# fmc.net
KiCad netlist of a schematic drawn in EAGLE
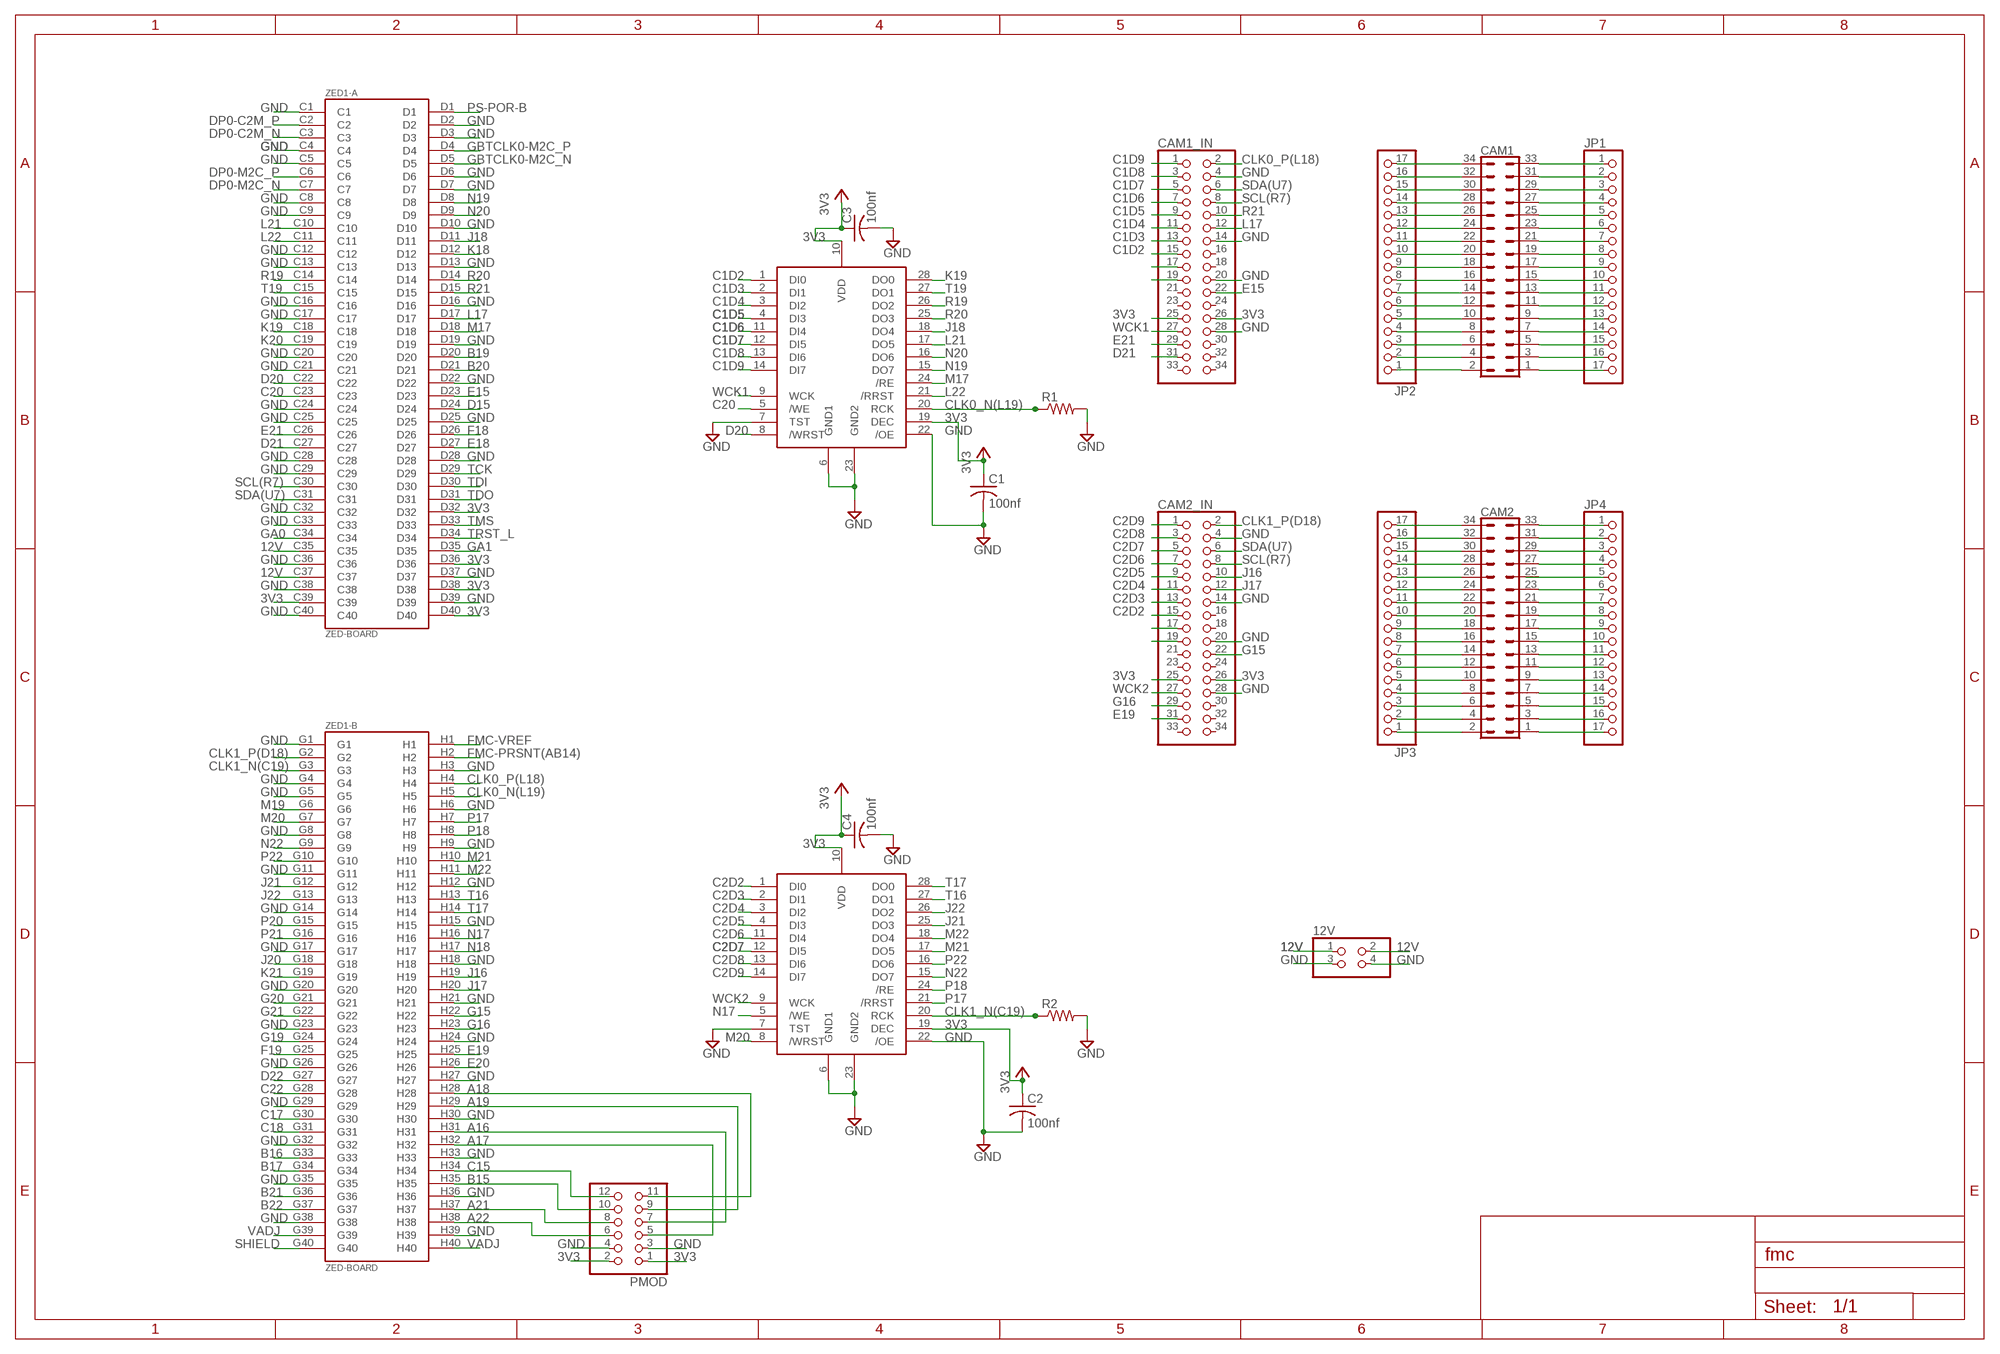
[diagram p0: schematic, sheet 1]

(export (version "E")
  (design (tool "Eeschema 10.0.6"))
  (components
    (comp (ref "12V")
      (value "PINHD-2X2")
      (footprint "eagle-import:2X02")
      (libsource (lib "eagle-import") (part "PINHD-2X2"))
    )
    (comp (ref "AL422B")
      (value "CAM1_FIFO")
      (footprint "eagle-import:SOP28")
      (libsource (lib "eagle-import") (part "AL422B"))
    )
    (comp (ref "C1")
      (value "100nf")
      (footprint "eagle-import:C025-024X044")
      (libsource (lib "eagle-import") (part "C-US025-024X044"))
    )
    (comp (ref "C2")
      (value "100nf")
      (footprint "eagle-import:C025-024X044")
      (libsource (lib "eagle-import") (part "C-US025-024X044"))
    )
    (comp (ref "C3")
      (value "100nf")
      (footprint "eagle-import:C025-024X044")
      (libsource (lib "eagle-import") (part "C-US025-024X044"))
    )
    (comp (ref "C4")
      (value "100nf")
      (footprint "eagle-import:C025-024X044")
      (libsource (lib "eagle-import") (part "C-US025-024X044"))
    )
    (comp (ref "CAM1")
      (value "PHB_1MM27_2X17_SNT")
      (footprint "eagle-import:PHB_1MM27_2X17_SNT")
      (libsource (lib "eagle-import") (part "PHB_1MM27_2X17_SNT"))
    )
    (comp (ref "CAM1_IN")
      (value "PINHD-2X17")
      (footprint "eagle-import:2X17")
      (libsource (lib "eagle-import") (part "PINHD-2X17"))
    )
    (comp (ref "CAM2")
      (value "PHB_1MM27_2X17_SNT")
      (footprint "eagle-import:PHB_1MM27_2X17_SNT")
      (libsource (lib "eagle-import") (part "PHB_1MM27_2X17_SNT"))
    )
    (comp (ref "CAM2_IN")
      (value "PINHD-2X17")
      (footprint "eagle-import:2X17")
      (libsource (lib "eagle-import") (part "PINHD-2X17"))
    )
    (comp (ref "JP1")
      (value "PINHD-1X17")
      (footprint "eagle-import:1X17")
      (libsource (lib "eagle-import") (part "PINHD-1X17"))
    )
    (comp (ref "JP2")
      (value "PINHD-1X17")
      (footprint "eagle-import:1X17")
      (libsource (lib "eagle-import") (part "PINHD-1X17"))
    )
    (comp (ref "JP3")
      (value "PINHD-1X17")
      (footprint "eagle-import:1X17")
      (libsource (lib "eagle-import") (part "PINHD-1X17"))
    )
    (comp (ref "JP4")
      (value "PINHD-1X17")
      (footprint "eagle-import:1X17")
      (libsource (lib "eagle-import") (part "PINHD-1X17"))
    )
    (comp (ref "PMOD")
      (value "PINHD-2X6")
      (footprint "eagle-import:2X06")
      (libsource (lib "eagle-import") (part "PINHD-2X6"))
    )
    (comp (ref "R1")
      (value "R-US_M0805")
      (footprint "eagle-import:M0805")
      (libsource (lib "eagle-import") (part "R-US_M0805"))
    )
    (comp (ref "R2")
      (value "R-US_M0805")
      (footprint "eagle-import:M0805")
      (libsource (lib "eagle-import") (part "R-US_M0805"))
    )
    (comp (ref "U$2")
      (value "CAM2_FIFO")
      (footprint "eagle-import:SOP28")
      (libsource (lib "eagle-import") (part "AL422B"))
    )
    (comp (ref "ZED1")
      (value "ZED-BOARD")
      (footprint "eagle-import:ASP-134604-01")
      (libsource (lib "eagle-import") (part "ZED-BOARD"))
    )
  )
  (nets
    (net (code "1") (name "/12V") (class "Default")
      (node (ref "12V") (pin "1") (pinfunction "1_1") (pintype "passive"))
      (node (ref "12V") (pin "2") (pinfunction "2_2") (pintype "passive"))
      (node (ref "ZED1") (pin "C35") (pinfunction "C35_C35") (pintype "bidirectional"))
      (node (ref "ZED1") (pin "C37") (pinfunction "C37_C37") (pintype "bidirectional"))
    )
    (net (code "2") (name "/A16") (class "Default")
      (node (ref "PMOD") (pin "7") (pinfunction "7_7") (pintype "passive"))
      (node (ref "ZED1") (pin "H31") (pinfunction "H31_H31") (pintype "bidirectional"))
    )
    (net (code "3") (name "/A17") (class "Default")
      (node (ref "PMOD") (pin "5") (pinfunction "5_5") (pintype "passive"))
      (node (ref "ZED1") (pin "H32") (pinfunction "H32_H32") (pintype "bidirectional"))
    )
    (net (code "4") (name "/A18") (class "Default")
      (node (ref "PMOD") (pin "11") (pinfunction "11_11") (pintype "passive"))
      (node (ref "ZED1") (pin "H28") (pinfunction "H28_H28") (pintype "bidirectional"))
    )
    (net (code "5") (name "/A19") (class "Default")
      (node (ref "PMOD") (pin "9") (pinfunction "9_9") (pintype "passive"))
      (node (ref "ZED1") (pin "H29") (pinfunction "H29_H29") (pintype "bidirectional"))
    )
    (net (code "6") (name "/A21") (class "Default")
      (node (ref "PMOD") (pin "8") (pinfunction "8_8") (pintype "passive"))
      (node (ref "ZED1") (pin "H37") (pinfunction "H37_H37") (pintype "bidirectional"))
    )
    (net (code "7") (name "/A22") (class "Default")
      (node (ref "PMOD") (pin "6") (pinfunction "6_6") (pintype "passive"))
      (node (ref "ZED1") (pin "H38") (pinfunction "H38_H38") (pintype "bidirectional"))
    )
    (net (code "8") (name "/B15") (class "Default")
      (node (ref "PMOD") (pin "10") (pinfunction "10_10") (pintype "passive"))
      (node (ref "ZED1") (pin "H35") (pinfunction "H35_H35") (pintype "bidirectional"))
    )
    (net (code "9") (name "/B16") (class "Default")
      (node (ref "ZED1") (pin "G33") (pinfunction "G33_G33") (pintype "bidirectional"))
    )
    (net (code "10") (name "/B17") (class "Default")
      (node (ref "ZED1") (pin "G34") (pinfunction "G34_G34") (pintype "bidirectional"))
    )
    (net (code "11") (name "/B19") (class "Default")
      (node (ref "ZED1") (pin "D20") (pinfunction "D20_D20") (pintype "bidirectional"))
    )
    (net (code "12") (name "/B20") (class "Default")
      (node (ref "ZED1") (pin "D21") (pinfunction "D21_D21") (pintype "bidirectional"))
    )
    (net (code "13") (name "/B21") (class "Default")
      (node (ref "ZED1") (pin "G36") (pinfunction "G36_G36") (pintype "bidirectional"))
    )
    (net (code "14") (name "/B22") (class "Default")
      (node (ref "ZED1") (pin "G37") (pinfunction "G37_G37") (pintype "bidirectional"))
    )
    (net (code "15") (name "/C1D2") (class "Default")
      (node (ref "AL422B") (pin "1") (pinfunction "DI0_1") (pintype "bidirectional"))
      (node (ref "CAM1_IN") (pin "15") (pinfunction "15_15") (pintype "passive"))
    )
    (net (code "16") (name "/C1D3") (class "Default")
      (node (ref "AL422B") (pin "2") (pinfunction "DI1_2") (pintype "bidirectional"))
      (node (ref "CAM1_IN") (pin "13") (pinfunction "13_13") (pintype "passive"))
    )
    (net (code "17") (name "/C1D4") (class "Default")
      (node (ref "AL422B") (pin "3") (pinfunction "DI2_3") (pintype "bidirectional"))
      (node (ref "CAM1_IN") (pin "11") (pinfunction "11_11") (pintype "passive"))
    )
    (net (code "18") (name "/C1D5") (class "Default")
      (node (ref "AL422B") (pin "4") (pinfunction "DI3_4") (pintype "bidirectional"))
      (node (ref "CAM1_IN") (pin "9") (pinfunction "9_9") (pintype "passive"))
    )
    (net (code "19") (name "/C1D6") (class "Default")
      (node (ref "AL422B") (pin "11") (pinfunction "DI4_11") (pintype "bidirectional"))
      (node (ref "CAM1_IN") (pin "7") (pinfunction "7_7") (pintype "passive"))
    )
    (net (code "20") (name "/C1D7") (class "Default")
      (node (ref "AL422B") (pin "12") (pinfunction "DI5_12") (pintype "bidirectional"))
      (node (ref "CAM1_IN") (pin "5") (pinfunction "5_5") (pintype "passive"))
    )
    (net (code "21") (name "/C1D8") (class "Default")
      (node (ref "AL422B") (pin "13") (pinfunction "DI6_13") (pintype "bidirectional"))
      (node (ref "CAM1_IN") (pin "3") (pinfunction "3_3") (pintype "passive"))
    )
    (net (code "22") (name "/C1D9") (class "Default")
      (node (ref "AL422B") (pin "14") (pinfunction "DI7_14") (pintype "bidirectional"))
      (node (ref "CAM1_IN") (pin "1") (pinfunction "1_1") (pintype "passive"))
    )
    (net (code "23") (name "/C2D2") (class "Default")
      (node (ref "CAM2_IN") (pin "15") (pinfunction "15_15") (pintype "passive"))
      (node (ref "U$2") (pin "1") (pinfunction "DI0_1") (pintype "bidirectional"))
    )
    (net (code "24") (name "/C2D3") (class "Default")
      (node (ref "CAM2_IN") (pin "13") (pinfunction "13_13") (pintype "passive"))
      (node (ref "U$2") (pin "2") (pinfunction "DI1_2") (pintype "bidirectional"))
    )
    (net (code "25") (name "/C2D4") (class "Default")
      (node (ref "CAM2_IN") (pin "11") (pinfunction "11_11") (pintype "passive"))
      (node (ref "U$2") (pin "3") (pinfunction "DI2_3") (pintype "bidirectional"))
    )
    (net (code "26") (name "/C2D5") (class "Default")
      (node (ref "CAM2_IN") (pin "9") (pinfunction "9_9") (pintype "passive"))
      (node (ref "U$2") (pin "4") (pinfunction "DI3_4") (pintype "bidirectional"))
    )
    (net (code "27") (name "/C2D6") (class "Default")
      (node (ref "CAM2_IN") (pin "7") (pinfunction "7_7") (pintype "passive"))
      (node (ref "U$2") (pin "11") (pinfunction "DI4_11") (pintype "bidirectional"))
    )
    (net (code "28") (name "/C2D7") (class "Default")
      (node (ref "CAM2_IN") (pin "5") (pinfunction "5_5") (pintype "passive"))
      (node (ref "U$2") (pin "12") (pinfunction "DI5_12") (pintype "bidirectional"))
    )
    (net (code "29") (name "/C2D8") (class "Default")
      (node (ref "CAM2_IN") (pin "3") (pinfunction "3_3") (pintype "passive"))
      (node (ref "U$2") (pin "13") (pinfunction "DI6_13") (pintype "bidirectional"))
    )
    (net (code "30") (name "/C2D9") (class "Default")
      (node (ref "CAM2_IN") (pin "1") (pinfunction "1_1") (pintype "passive"))
      (node (ref "U$2") (pin "14") (pinfunction "DI7_14") (pintype "bidirectional"))
    )
    (net (code "31") (name "/C15") (class "Default")
      (node (ref "PMOD") (pin "12") (pinfunction "12_12") (pintype "passive"))
      (node (ref "ZED1") (pin "H34") (pinfunction "H34_H34") (pintype "bidirectional"))
    )
    (net (code "32") (name "/C17") (class "Default")
      (node (ref "ZED1") (pin "G30") (pinfunction "G30_G30") (pintype "bidirectional"))
    )
    (net (code "33") (name "/C18") (class "Default")
      (node (ref "ZED1") (pin "G31") (pinfunction "G31_G31") (pintype "bidirectional"))
    )
    (net (code "34") (name "/C20") (class "Default")
      (node (ref "AL422B") (pin "5") (pinfunction "/WE_5") (pintype "bidirectional"))
      (node (ref "ZED1") (pin "C23") (pinfunction "C23_C23") (pintype "bidirectional"))
    )
    (net (code "35") (name "/C22") (class "Default")
      (node (ref "ZED1") (pin "G28") (pinfunction "G28_G28") (pintype "bidirectional"))
    )
    (net (code "36") (name "/CLK0_N(L19)") (class "Default")
      (node (ref "AL422B") (pin "20") (pinfunction "RCK_20") (pintype "bidirectional"))
      (node (ref "R1") (pin "1") (pinfunction "1_1") (pintype "passive"))
      (node (ref "ZED1") (pin "H5") (pinfunction "H5_H5") (pintype "bidirectional"))
    )
    (net (code "37") (name "/CLK0_P(L18)") (class "Default")
      (node (ref "CAM1_IN") (pin "2") (pinfunction "2_2") (pintype "passive"))
      (node (ref "ZED1") (pin "H4") (pinfunction "H4_H4") (pintype "bidirectional"))
    )
    (net (code "38") (name "/CLK1_N(C19)") (class "Default")
      (node (ref "R2") (pin "1") (pinfunction "1_1") (pintype "passive"))
      (node (ref "U$2") (pin "20") (pinfunction "RCK_20") (pintype "bidirectional"))
      (node (ref "ZED1") (pin "G3") (pinfunction "G3_G3") (pintype "bidirectional"))
    )
    (net (code "39") (name "/CLK1_P(D18)") (class "Default")
      (node (ref "CAM2_IN") (pin "2") (pinfunction "2_2") (pintype "passive"))
      (node (ref "ZED1") (pin "G2") (pinfunction "G2_G2") (pintype "bidirectional"))
    )
    (net (code "40") (name "/D15") (class "Default")
      (node (ref "ZED1") (pin "D24") (pinfunction "D24_D24") (pintype "bidirectional"))
    )
    (net (code "41") (name "/D20") (class "Default")
      (node (ref "AL422B") (pin "8") (pinfunction "/WRST_8") (pintype "bidirectional"))
      (node (ref "ZED1") (pin "C22") (pinfunction "C22_C22") (pintype "bidirectional"))
    )
    (net (code "42") (name "/D21") (class "Default")
      (node (ref "CAM1_IN") (pin "31") (pinfunction "31_31") (pintype "passive"))
      (node (ref "ZED1") (pin "C27") (pinfunction "C27_C27") (pintype "bidirectional"))
    )
    (net (code "43") (name "/D22") (class "Default")
      (node (ref "ZED1") (pin "G27") (pinfunction "G27_G27") (pintype "bidirectional"))
    )
    (net (code "44") (name "/DP0-C2M_N") (class "Default")
      (node (ref "ZED1") (pin "C3") (pinfunction "C3_C3") (pintype "bidirectional"))
    )
    (net (code "45") (name "/DP0-C2M_P") (class "Default")
      (node (ref "ZED1") (pin "C2") (pinfunction "C2_C2") (pintype "bidirectional"))
    )
    (net (code "46") (name "/DP0-M2C_N") (class "Default")
      (node (ref "ZED1") (pin "C7") (pinfunction "C7_C7") (pintype "bidirectional"))
    )
    (net (code "47") (name "/DP0-M2C_P") (class "Default")
      (node (ref "ZED1") (pin "C6") (pinfunction "C6_C6") (pintype "bidirectional"))
    )
    (net (code "48") (name "/E15") (class "Default")
      (node (ref "CAM1_IN") (pin "22") (pinfunction "22_22") (pintype "passive"))
      (node (ref "ZED1") (pin "D23") (pinfunction "D23_D23") (pintype "bidirectional"))
    )
    (net (code "49") (name "/E18") (class "Default")
      (node (ref "ZED1") (pin "D27") (pinfunction "D27_D27") (pintype "bidirectional"))
    )
    (net (code "50") (name "/E19") (class "Default")
      (node (ref "CAM2_IN") (pin "31") (pinfunction "31_31") (pintype "passive"))
      (node (ref "ZED1") (pin "H25") (pinfunction "H25_H25") (pintype "bidirectional"))
    )
    (net (code "51") (name "/E20") (class "Default")
      (node (ref "ZED1") (pin "H26") (pinfunction "H26_H26") (pintype "bidirectional"))
    )
    (net (code "52") (name "/E21") (class "Default")
      (node (ref "CAM1_IN") (pin "29") (pinfunction "29_29") (pintype "passive"))
      (node (ref "ZED1") (pin "C26") (pinfunction "C26_C26") (pintype "bidirectional"))
    )
    (net (code "53") (name "/F18") (class "Default")
      (node (ref "ZED1") (pin "D26") (pinfunction "D26_D26") (pintype "bidirectional"))
    )
    (net (code "54") (name "/F19") (class "Default")
      (node (ref "ZED1") (pin "G25") (pinfunction "G25_G25") (pintype "bidirectional"))
    )
    (net (code "55") (name "/FMC-PRSNT(AB14)") (class "Default")
      (node (ref "ZED1") (pin "H2") (pinfunction "H2_H2") (pintype "bidirectional"))
    )
    (net (code "56") (name "/FMC-VREF") (class "Default")
      (node (ref "ZED1") (pin "H1") (pinfunction "H1_H1") (pintype "bidirectional"))
    )
    (net (code "57") (name "/G15") (class "Default")
      (node (ref "CAM2_IN") (pin "22") (pinfunction "22_22") (pintype "passive"))
      (node (ref "ZED1") (pin "H22") (pinfunction "H22_H22") (pintype "bidirectional"))
    )
    (net (code "58") (name "/G16") (class "Default")
      (node (ref "CAM2_IN") (pin "29") (pinfunction "29_29") (pintype "passive"))
      (node (ref "ZED1") (pin "H23") (pinfunction "H23_H23") (pintype "bidirectional"))
    )
    (net (code "59") (name "/G19") (class "Default")
      (node (ref "ZED1") (pin "G24") (pinfunction "G24_G24") (pintype "bidirectional"))
    )
    (net (code "60") (name "/G20") (class "Default")
      (node (ref "ZED1") (pin "G21") (pinfunction "G21_G21") (pintype "bidirectional"))
    )
    (net (code "61") (name "/G21") (class "Default")
      (node (ref "ZED1") (pin "G22") (pinfunction "G22_G22") (pintype "bidirectional"))
    )
    (net (code "62") (name "/GA0") (class "Default")
      (node (ref "ZED1") (pin "C34") (pinfunction "C34_C34") (pintype "bidirectional"))
    )
    (net (code "63") (name "/GA1") (class "Default")
      (node (ref "ZED1") (pin "D35") (pinfunction "D35_D35") (pintype "bidirectional"))
    )
    (net (code "64") (name "/GBTCLK0-M2C_N") (class "Default")
      (node (ref "ZED1") (pin "D5") (pinfunction "D5_D5") (pintype "bidirectional"))
    )
    (net (code "65") (name "/GBTCLK0-M2C_P") (class "Default")
      (node (ref "ZED1") (pin "D4") (pinfunction "D4_D4") (pintype "bidirectional"))
    )
    (net (code "66") (name "/J16") (class "Default")
      (node (ref "CAM2_IN") (pin "10") (pinfunction "10_10") (pintype "passive"))
      (node (ref "ZED1") (pin "H19") (pinfunction "H19_H19") (pintype "bidirectional"))
    )
    (net (code "67") (name "/J17") (class "Default")
      (node (ref "CAM2_IN") (pin "12") (pinfunction "12_12") (pintype "passive"))
      (node (ref "ZED1") (pin "H20") (pinfunction "H20_H20") (pintype "bidirectional"))
    )
    (net (code "68") (name "/J18") (class "Default")
      (node (ref "AL422B") (pin "18") (pinfunction "DO4_18") (pintype "bidirectional"))
      (node (ref "ZED1") (pin "D11") (pinfunction "D11_D11") (pintype "bidirectional"))
    )
    (net (code "69") (name "/J20") (class "Default")
      (node (ref "ZED1") (pin "G18") (pinfunction "G18_G18") (pintype "bidirectional"))
    )
    (net (code "70") (name "/J21") (class "Default")
      (node (ref "U$2") (pin "25") (pinfunction "DO3_25") (pintype "bidirectional"))
      (node (ref "ZED1") (pin "G12") (pinfunction "G12_G12") (pintype "bidirectional"))
    )
    (net (code "71") (name "/J22") (class "Default")
      (node (ref "U$2") (pin "26") (pinfunction "DO2_26") (pintype "bidirectional"))
      (node (ref "ZED1") (pin "G13") (pinfunction "G13_G13") (pintype "bidirectional"))
    )
    (net (code "72") (name "/K18") (class "Default")
      (node (ref "ZED1") (pin "D12") (pinfunction "D12_D12") (pintype "bidirectional"))
    )
    (net (code "73") (name "/K19") (class "Default")
      (node (ref "AL422B") (pin "28") (pinfunction "DO0_28") (pintype "bidirectional"))
      (node (ref "ZED1") (pin "C18") (pinfunction "C18_C18") (pintype "bidirectional"))
    )
    (net (code "74") (name "/K20") (class "Default")
      (node (ref "ZED1") (pin "C19") (pinfunction "C19_C19") (pintype "bidirectional"))
    )
    (net (code "75") (name "/K21") (class "Default")
      (node (ref "ZED1") (pin "G19") (pinfunction "G19_G19") (pintype "bidirectional"))
    )
    (net (code "76") (name "/L17") (class "Default")
      (node (ref "CAM1_IN") (pin "12") (pinfunction "12_12") (pintype "passive"))
      (node (ref "ZED1") (pin "D17") (pinfunction "D17_D17") (pintype "bidirectional"))
    )
    (net (code "77") (name "/L21") (class "Default")
      (node (ref "AL422B") (pin "17") (pinfunction "DO5_17") (pintype "bidirectional"))
      (node (ref "ZED1") (pin "C10") (pinfunction "C10_C10") (pintype "bidirectional"))
    )
    (net (code "78") (name "/L22") (class "Default")
      (node (ref "AL422B") (pin "21") (pinfunction "/RRST_21") (pintype "bidirectional"))
      (node (ref "ZED1") (pin "C11") (pinfunction "C11_C11") (pintype "bidirectional"))
    )
    (net (code "79") (name "/M17") (class "Default")
      (node (ref "AL422B") (pin "24") (pinfunction "/RE_24") (pintype "bidirectional"))
      (node (ref "ZED1") (pin "D18") (pinfunction "D18_D18") (pintype "bidirectional"))
    )
    (net (code "80") (name "/M19") (class "Default")
      (node (ref "ZED1") (pin "G6") (pinfunction "G6_G6") (pintype "bidirectional"))
    )
    (net (code "81") (name "/M20") (class "Default")
      (node (ref "U$2") (pin "8") (pinfunction "/WRST_8") (pintype "bidirectional"))
      (node (ref "ZED1") (pin "G7") (pinfunction "G7_G7") (pintype "bidirectional"))
    )
    (net (code "82") (name "/M21") (class "Default")
      (node (ref "U$2") (pin "17") (pinfunction "DO5_17") (pintype "bidirectional"))
      (node (ref "ZED1") (pin "H10") (pinfunction "H10_H10") (pintype "bidirectional"))
    )
    (net (code "83") (name "/M22") (class "Default")
      (node (ref "U$2") (pin "18") (pinfunction "DO4_18") (pintype "bidirectional"))
      (node (ref "ZED1") (pin "H11") (pinfunction "H11_H11") (pintype "bidirectional"))
    )
    (net (code "84") (name "/N17") (class "Default")
      (node (ref "U$2") (pin "5") (pinfunction "/WE_5") (pintype "bidirectional"))
      (node (ref "ZED1") (pin "H16") (pinfunction "H16_H16") (pintype "bidirectional"))
    )
    (net (code "85") (name "/N18") (class "Default")
      (node (ref "ZED1") (pin "H17") (pinfunction "H17_H17") (pintype "bidirectional"))
    )
    (net (code "86") (name "/N19") (class "Default")
      (node (ref "AL422B") (pin "15") (pinfunction "DO7_15") (pintype "bidirectional"))
      (node (ref "ZED1") (pin "D8") (pinfunction "D8_D8") (pintype "bidirectional"))
    )
    (net (code "87") (name "/N20") (class "Default")
      (node (ref "AL422B") (pin "16") (pinfunction "DO6_16") (pintype "bidirectional"))
      (node (ref "ZED1") (pin "D9") (pinfunction "D9_D9") (pintype "bidirectional"))
    )
    (net (code "88") (name "/N22") (class "Default")
      (node (ref "U$2") (pin "15") (pinfunction "DO7_15") (pintype "bidirectional"))
      (node (ref "ZED1") (pin "G9") (pinfunction "G9_G9") (pintype "bidirectional"))
    )
    (net (code "89") (name "/P17") (class "Default")
      (node (ref "U$2") (pin "21") (pinfunction "/RRST_21") (pintype "bidirectional"))
      (node (ref "ZED1") (pin "H7") (pinfunction "H7_H7") (pintype "bidirectional"))
    )
    (net (code "90") (name "/P18") (class "Default")
      (node (ref "U$2") (pin "24") (pinfunction "/RE_24") (pintype "bidirectional"))
      (node (ref "ZED1") (pin "H8") (pinfunction "H8_H8") (pintype "bidirectional"))
    )
    (net (code "91") (name "/P20") (class "Default")
      (node (ref "ZED1") (pin "G15") (pinfunction "G15_G15") (pintype "bidirectional"))
    )
    (net (code "92") (name "/P21") (class "Default")
      (node (ref "ZED1") (pin "G16") (pinfunction "G16_G16") (pintype "bidirectional"))
    )
    (net (code "93") (name "/P22") (class "Default")
      (node (ref "U$2") (pin "16") (pinfunction "DO6_16") (pintype "bidirectional"))
      (node (ref "ZED1") (pin "G10") (pinfunction "G10_G10") (pintype "bidirectional"))
    )
    (net (code "94") (name "/PS-POR-B") (class "Default")
      (node (ref "ZED1") (pin "D1") (pinfunction "D1_D1") (pintype "bidirectional"))
    )
    (net (code "95") (name "/R19") (class "Default")
      (node (ref "AL422B") (pin "26") (pinfunction "DO2_26") (pintype "bidirectional"))
      (node (ref "ZED1") (pin "C14") (pinfunction "C14_C14") (pintype "bidirectional"))
    )
    (net (code "96") (name "/R20") (class "Default")
      (node (ref "AL422B") (pin "25") (pinfunction "DO3_25") (pintype "bidirectional"))
      (node (ref "ZED1") (pin "D14") (pinfunction "D14_D14") (pintype "bidirectional"))
    )
    (net (code "97") (name "/R21") (class "Default")
      (node (ref "CAM1_IN") (pin "10") (pinfunction "10_10") (pintype "passive"))
      (node (ref "ZED1") (pin "D15") (pinfunction "D15_D15") (pintype "bidirectional"))
    )
    (net (code "98") (name "/SCL(R7)") (class "Default")
      (node (ref "CAM1_IN") (pin "8") (pinfunction "8_8") (pintype "passive"))
      (node (ref "CAM2_IN") (pin "8") (pinfunction "8_8") (pintype "passive"))
      (node (ref "ZED1") (pin "C30") (pinfunction "C30_C30") (pintype "bidirectional"))
    )
    (net (code "99") (name "/SDA(U7)") (class "Default")
      (node (ref "CAM1_IN") (pin "6") (pinfunction "6_6") (pintype "passive"))
      (node (ref "CAM2_IN") (pin "6") (pinfunction "6_6") (pintype "passive"))
      (node (ref "ZED1") (pin "C31") (pinfunction "C31_C31") (pintype "bidirectional"))
    )
    (net (code "100") (name "/SHIELD") (class "Default")
      (node (ref "ZED1") (pin "G40") (pinfunction "G40_G40") (pintype "bidirectional"))
    )
    (net (code "101") (name "/T16") (class "Default")
      (node (ref "U$2") (pin "27") (pinfunction "DO1_27") (pintype "bidirectional"))
      (node (ref "ZED1") (pin "H13") (pinfunction "H13_H13") (pintype "bidirectional"))
    )
    (net (code "102") (name "/T17") (class "Default")
      (node (ref "U$2") (pin "28") (pinfunction "DO0_28") (pintype "bidirectional"))
      (node (ref "ZED1") (pin "H14") (pinfunction "H14_H14") (pintype "bidirectional"))
    )
    (net (code "103") (name "/T19") (class "Default")
      (node (ref "AL422B") (pin "27") (pinfunction "DO1_27") (pintype "bidirectional"))
      (node (ref "ZED1") (pin "C15") (pinfunction "C15_C15") (pintype "bidirectional"))
    )
    (net (code "104") (name "/TCK") (class "Default")
      (node (ref "ZED1") (pin "D29") (pinfunction "D29_D29") (pintype "bidirectional"))
    )
    (net (code "105") (name "/TDI") (class "Default")
      (node (ref "ZED1") (pin "D30") (pinfunction "D30_D30") (pintype "bidirectional"))
    )
    (net (code "106") (name "/TDO") (class "Default")
      (node (ref "ZED1") (pin "D31") (pinfunction "D31_D31") (pintype "bidirectional"))
    )
    (net (code "107") (name "/TMS") (class "Default")
      (node (ref "ZED1") (pin "D33") (pinfunction "D33_D33") (pintype "bidirectional"))
    )
    (net (code "108") (name "/TRST_L") (class "Default")
      (node (ref "ZED1") (pin "D34") (pinfunction "D34_D34") (pintype "bidirectional"))
    )
    (net (code "109") (name "/VADJ") (class "Default")
      (node (ref "ZED1") (pin "G39") (pinfunction "G39_G39") (pintype "bidirectional"))
      (node (ref "ZED1") (pin "H40") (pinfunction "H40_H40") (pintype "bidirectional"))
    )
    (net (code "110") (name "/WCK1") (class "Default")
      (node (ref "AL422B") (pin "9") (pinfunction "WCK_9") (pintype "bidirectional"))
      (node (ref "CAM1_IN") (pin "27") (pinfunction "27_27") (pintype "passive"))
    )
    (net (code "111") (name "/WCK2") (class "Default")
      (node (ref "CAM2_IN") (pin "27") (pinfunction "27_27") (pintype "passive"))
      (node (ref "U$2") (pin "9") (pinfunction "WCK_9") (pintype "bidirectional"))
    )
    (net (code "112") (name "3V3") (class "Default")
      (node (ref "AL422B") (pin "10") (pinfunction "VDD_10") (pintype "power_in"))
      (node (ref "AL422B") (pin "19") (pinfunction "DEC_19") (pintype "bidirectional"))
      (node (ref "C1") (pin "1") (pinfunction "1_1") (pintype "passive"))
      (node (ref "C2") (pin "1") (pinfunction "1_1") (pintype "passive"))
      (node (ref "C3") (pin "1") (pinfunction "1_1") (pintype "passive"))
      (node (ref "C4") (pin "1") (pinfunction "1_1") (pintype "passive"))
      (node (ref "CAM1_IN") (pin "25") (pinfunction "25_25") (pintype "passive"))
      (node (ref "CAM1_IN") (pin "26") (pinfunction "26_26") (pintype "passive"))
      (node (ref "CAM2_IN") (pin "25") (pinfunction "25_25") (pintype "passive"))
      (node (ref "CAM2_IN") (pin "26") (pinfunction "26_26") (pintype "passive"))
      (node (ref "PMOD") (pin "1") (pinfunction "1_1") (pintype "passive"))
      (node (ref "PMOD") (pin "2") (pinfunction "2_2") (pintype "passive"))
      (node (ref "U$2") (pin "10") (pinfunction "VDD_10") (pintype "power_in"))
      (node (ref "U$2") (pin "19") (pinfunction "DEC_19") (pintype "bidirectional"))
      (node (ref "ZED1") (pin "C39") (pinfunction "C39_C39") (pintype "bidirectional"))
      (node (ref "ZED1") (pin "D32") (pinfunction "D32_D32") (pintype "bidirectional"))
      (node (ref "ZED1") (pin "D36") (pinfunction "D36_D36") (pintype "bidirectional"))
      (node (ref "ZED1") (pin "D38") (pinfunction "D38_D38") (pintype "bidirectional"))
      (node (ref "ZED1") (pin "D40") (pinfunction "D40_D40") (pintype "bidirectional"))
    )
    (net (code "113") (name "GND") (class "Default")
      (node (ref "12V") (pin "3") (pinfunction "3_3") (pintype "passive"))
      (node (ref "12V") (pin "4") (pinfunction "4_4") (pintype "passive"))
      (node (ref "AL422B") (pin "22") (pinfunction "/OE_22") (pintype "bidirectional"))
      (node (ref "AL422B") (pin "23") (pinfunction "GND2_23") (pintype "power_in"))
      (node (ref "AL422B") (pin "6") (pinfunction "GND1_6") (pintype "power_in"))
      (node (ref "AL422B") (pin "7") (pinfunction "TST_7") (pintype "bidirectional"))
      (node (ref "C1") (pin "2") (pinfunction "2_2") (pintype "passive"))
      (node (ref "C2") (pin "2") (pinfunction "2_2") (pintype "passive"))
      (node (ref "C3") (pin "2") (pinfunction "2_2") (pintype "passive"))
      (node (ref "C4") (pin "2") (pinfunction "2_2") (pintype "passive"))
      (node (ref "CAM1_IN") (pin "14") (pinfunction "14_14") (pintype "passive"))
      (node (ref "CAM1_IN") (pin "20") (pinfunction "20_20") (pintype "passive"))
      (node (ref "CAM1_IN") (pin "28") (pinfunction "28_28") (pintype "passive"))
      (node (ref "CAM1_IN") (pin "4") (pinfunction "4_4") (pintype "passive"))
      (node (ref "CAM2_IN") (pin "14") (pinfunction "14_14") (pintype "passive"))
      (node (ref "CAM2_IN") (pin "20") (pinfunction "20_20") (pintype "passive"))
      (node (ref "CAM2_IN") (pin "28") (pinfunction "28_28") (pintype "passive"))
      (node (ref "CAM2_IN") (pin "4") (pinfunction "4_4") (pintype "passive"))
      (node (ref "PMOD") (pin "3") (pinfunction "3_3") (pintype "passive"))
      (node (ref "PMOD") (pin "4") (pinfunction "4_4") (pintype "passive"))
      (node (ref "R1") (pin "2") (pinfunction "2_2") (pintype "passive"))
      (node (ref "R2") (pin "2") (pinfunction "2_2") (pintype "passive"))
      (node (ref "U$2") (pin "22") (pinfunction "/OE_22") (pintype "bidirectional"))
      (node (ref "U$2") (pin "23") (pinfunction "GND2_23") (pintype "power_in"))
      (node (ref "U$2") (pin "6") (pinfunction "GND1_6") (pintype "power_in"))
      (node (ref "U$2") (pin "7") (pinfunction "TST_7") (pintype "bidirectional"))
      (node (ref "ZED1") (pin "C1") (pinfunction "C1_C1") (pintype "bidirectional"))
      (node (ref "ZED1") (pin "C12") (pinfunction "C12_C12") (pintype "bidirectional"))
      (node (ref "ZED1") (pin "C13") (pinfunction "C13_C13") (pintype "bidirectional"))
      (node (ref "ZED1") (pin "C16") (pinfunction "C16_C16") (pintype "bidirectional"))
      (node (ref "ZED1") (pin "C17") (pinfunction "C17_C17") (pintype "bidirectional"))
      (node (ref "ZED1") (pin "C20") (pinfunction "C20_C20") (pintype "bidirectional"))
      (node (ref "ZED1") (pin "C21") (pinfunction "C21_C21") (pintype "bidirectional"))
      (node (ref "ZED1") (pin "C24") (pinfunction "C24_C24") (pintype "bidirectional"))
      (node (ref "ZED1") (pin "C25") (pinfunction "C25_C25") (pintype "bidirectional"))
      (node (ref "ZED1") (pin "C28") (pinfunction "C28_C28") (pintype "bidirectional"))
      (node (ref "ZED1") (pin "C29") (pinfunction "C29_C29") (pintype "bidirectional"))
      (node (ref "ZED1") (pin "C32") (pinfunction "C32_C32") (pintype "bidirectional"))
      (node (ref "ZED1") (pin "C33") (pinfunction "C33_C33") (pintype "bidirectional"))
      (node (ref "ZED1") (pin "C36") (pinfunction "C36_C36") (pintype "bidirectional"))
      (node (ref "ZED1") (pin "C38") (pinfunction "C38_C38") (pintype "bidirectional"))
      (node (ref "ZED1") (pin "C4") (pinfunction "C4_C4") (pintype "bidirectional"))
      (node (ref "ZED1") (pin "C40") (pinfunction "C40_C40") (pintype "bidirectional"))
      (node (ref "ZED1") (pin "C5") (pinfunction "C5_C5") (pintype "bidirectional"))
      (node (ref "ZED1") (pin "C8") (pinfunction "C8_C8") (pintype "bidirectional"))
      (node (ref "ZED1") (pin "C9") (pinfunction "C9_C9") (pintype "bidirectional"))
      (node (ref "ZED1") (pin "D10") (pinfunction "D10_D10") (pintype "bidirectional"))
      (node (ref "ZED1") (pin "D13") (pinfunction "D13_D13") (pintype "bidirectional"))
      (node (ref "ZED1") (pin "D16") (pinfunction "D16_D16") (pintype "bidirectional"))
      (node (ref "ZED1") (pin "D19") (pinfunction "D19_D19") (pintype "bidirectional"))
      (node (ref "ZED1") (pin "D2") (pinfunction "D2_D2") (pintype "bidirectional"))
      (node (ref "ZED1") (pin "D22") (pinfunction "D22_D22") (pintype "bidirectional"))
      (node (ref "ZED1") (pin "D25") (pinfunction "D25_D25") (pintype "bidirectional"))
      (node (ref "ZED1") (pin "D28") (pinfunction "D28_D28") (pintype "bidirectional"))
      (node (ref "ZED1") (pin "D3") (pinfunction "D3_D3") (pintype "bidirectional"))
      (node (ref "ZED1") (pin "D37") (pinfunction "D37_D37") (pintype "bidirectional"))
      (node (ref "ZED1") (pin "D39") (pinfunction "D39_D39") (pintype "bidirectional"))
      (node (ref "ZED1") (pin "D6") (pinfunction "D6_D6") (pintype "bidirectional"))
      (node (ref "ZED1") (pin "D7") (pinfunction "D7_D7") (pintype "bidirectional"))
      (node (ref "ZED1") (pin "G1") (pinfunction "G1_G1") (pintype "bidirectional"))
      (node (ref "ZED1") (pin "G11") (pinfunction "G11_G11") (pintype "bidirectional"))
      (node (ref "ZED1") (pin "G14") (pinfunction "G14_G14") (pintype "bidirectional"))
      (node (ref "ZED1") (pin "G17") (pinfunction "G17_G17") (pintype "bidirectional"))
      (node (ref "ZED1") (pin "G20") (pinfunction "G20_G20") (pintype "bidirectional"))
      (node (ref "ZED1") (pin "G23") (pinfunction "G23_G23") (pintype "bidirectional"))
      (node (ref "ZED1") (pin "G26") (pinfunction "G26_G26") (pintype "bidirectional"))
      (node (ref "ZED1") (pin "G29") (pinfunction "G29_G29") (pintype "bidirectional"))
      (node (ref "ZED1") (pin "G32") (pinfunction "G32_G32") (pintype "bidirectional"))
      (node (ref "ZED1") (pin "G35") (pinfunction "G35_G35") (pintype "bidirectional"))
      (node (ref "ZED1") (pin "G38") (pinfunction "G38_G38") (pintype "bidirectional"))
      (node (ref "ZED1") (pin "G4") (pinfunction "G4_G4") (pintype "bidirectional"))
      (node (ref "ZED1") (pin "G5") (pinfunction "G5_G5") (pintype "bidirectional"))
      (node (ref "ZED1") (pin "G8") (pinfunction "G8_G8") (pintype "bidirectional"))
      (node (ref "ZED1") (pin "H12") (pinfunction "H12_H12") (pintype "bidirectional"))
      (node (ref "ZED1") (pin "H15") (pinfunction "H15_H15") (pintype "bidirectional"))
      (node (ref "ZED1") (pin "H18") (pinfunction "H18_H18") (pintype "bidirectional"))
      (node (ref "ZED1") (pin "H21") (pinfunction "H21_H21") (pintype "bidirectional"))
      (node (ref "ZED1") (pin "H24") (pinfunction "H24_H24") (pintype "bidirectional"))
      (node (ref "ZED1") (pin "H27") (pinfunction "H27_H27") (pintype "bidirectional"))
      (node (ref "ZED1") (pin "H3") (pinfunction "H3_H3") (pintype "bidirectional"))
      (node (ref "ZED1") (pin "H30") (pinfunction "H30_H30") (pintype "bidirectional"))
      (node (ref "ZED1") (pin "H33") (pinfunction "H33_H33") (pintype "bidirectional"))
      (node (ref "ZED1") (pin "H36") (pinfunction "H36_H36") (pintype "bidirectional"))
      (node (ref "ZED1") (pin "H39") (pinfunction "H39_H39") (pintype "bidirectional"))
      (node (ref "ZED1") (pin "H6") (pinfunction "H6_H6") (pintype "bidirectional"))
      (node (ref "ZED1") (pin "H9") (pinfunction "H9_H9") (pintype "bidirectional"))
    )
    (net (code "114") (name "Net-(CAM1-Pad1)") (class "Default")
      (node (ref "CAM1") (pin "1") (pinfunction "1_1") (pintype "passive"))
      (node (ref "JP1") (pin "17") (pinfunction "17_17") (pintype "passive"))
    )
    (net (code "115") (name "Net-(CAM1-Pad2)") (class "Default")
      (node (ref "CAM1") (pin "2") (pinfunction "2_2") (pintype "passive"))
      (node (ref "JP2") (pin "1") (pinfunction "1_1") (pintype "passive"))
    )
    (net (code "116") (name "Net-(CAM1-Pad3)") (class "Default")
      (node (ref "CAM1") (pin "3") (pinfunction "3_3") (pintype "passive"))
      (node (ref "JP1") (pin "16") (pinfunction "16_16") (pintype "passive"))
    )
    (net (code "117") (name "Net-(CAM1-Pad4)") (class "Default")
      (node (ref "CAM1") (pin "4") (pinfunction "4_4") (pintype "passive"))
      (node (ref "JP2") (pin "2") (pinfunction "2_2") (pintype "passive"))
    )
    (net (code "118") (name "Net-(CAM1-Pad5)") (class "Default")
      (node (ref "CAM1") (pin "5") (pinfunction "5_5") (pintype "passive"))
      (node (ref "JP1") (pin "15") (pinfunction "15_15") (pintype "passive"))
    )
    (net (code "119") (name "Net-(CAM1-Pad6)") (class "Default")
      (node (ref "CAM1") (pin "6") (pinfunction "6_6") (pintype "passive"))
      (node (ref "JP2") (pin "3") (pinfunction "3_3") (pintype "passive"))
    )
    (net (code "120") (name "Net-(CAM1-Pad7)") (class "Default")
      (node (ref "CAM1") (pin "7") (pinfunction "7_7") (pintype "passive"))
      (node (ref "JP1") (pin "14") (pinfunction "14_14") (pintype "passive"))
    )
    (net (code "121") (name "Net-(CAM1-Pad8)") (class "Default")
      (node (ref "CAM1") (pin "8") (pinfunction "8_8") (pintype "passive"))
      (node (ref "JP2") (pin "4") (pinfunction "4_4") (pintype "passive"))
    )
    (net (code "122") (name "Net-(CAM1-Pad9)") (class "Default")
      (node (ref "CAM1") (pin "9") (pinfunction "9_9") (pintype "passive"))
      (node (ref "JP1") (pin "13") (pinfunction "13_13") (pintype "passive"))
    )
    (net (code "123") (name "Net-(CAM1-Pad10)") (class "Default")
      (node (ref "CAM1") (pin "10") (pinfunction "10_10") (pintype "passive"))
      (node (ref "JP2") (pin "5") (pinfunction "5_5") (pintype "passive"))
    )
    (net (code "124") (name "Net-(CAM1-Pad11)") (class "Default")
      (node (ref "CAM1") (pin "11") (pinfunction "11_11") (pintype "passive"))
      (node (ref "JP1") (pin "12") (pinfunction "12_12") (pintype "passive"))
    )
    (net (code "125") (name "Net-(CAM1-Pad12)") (class "Default")
      (node (ref "CAM1") (pin "12") (pinfunction "12_12") (pintype "passive"))
      (node (ref "JP2") (pin "6") (pinfunction "6_6") (pintype "passive"))
    )
    (net (code "126") (name "Net-(CAM1-Pad13)") (class "Default")
      (node (ref "CAM1") (pin "13") (pinfunction "13_13") (pintype "passive"))
      (node (ref "JP1") (pin "11") (pinfunction "11_11") (pintype "passive"))
    )
    (net (code "127") (name "Net-(CAM1-Pad14)") (class "Default")
      (node (ref "CAM1") (pin "14") (pinfunction "14_14") (pintype "passive"))
      (node (ref "JP2") (pin "7") (pinfunction "7_7") (pintype "passive"))
    )
    (net (code "128") (name "Net-(CAM1-Pad15)") (class "Default")
      (node (ref "CAM1") (pin "15") (pinfunction "15_15") (pintype "passive"))
      (node (ref "JP1") (pin "10") (pinfunction "10_10") (pintype "passive"))
    )
    (net (code "129") (name "Net-(CAM1-Pad16)") (class "Default")
      (node (ref "CAM1") (pin "16") (pinfunction "16_16") (pintype "passive"))
      (node (ref "JP2") (pin "8") (pinfunction "8_8") (pintype "passive"))
    )
    (net (code "130") (name "Net-(CAM1-Pad17)") (class "Default")
      (node (ref "CAM1") (pin "17") (pinfunction "17_17") (pintype "passive"))
      (node (ref "JP1") (pin "9") (pinfunction "9_9") (pintype "passive"))
    )
    (net (code "131") (name "Net-(CAM1-Pad18)") (class "Default")
      (node (ref "CAM1") (pin "18") (pinfunction "18_18") (pintype "passive"))
      (node (ref "JP2") (pin "9") (pinfunction "9_9") (pintype "passive"))
    )
    (net (code "132") (name "Net-(CAM1-Pad19)") (class "Default")
      (node (ref "CAM1") (pin "19") (pinfunction "19_19") (pintype "passive"))
      (node (ref "JP1") (pin "8") (pinfunction "8_8") (pintype "passive"))
    )
    (net (code "133") (name "Net-(CAM1-Pad20)") (class "Default")
      (node (ref "CAM1") (pin "20") (pinfunction "20_20") (pintype "passive"))
      (node (ref "JP2") (pin "10") (pinfunction "10_10") (pintype "passive"))
    )
    (net (code "134") (name "Net-(CAM1-Pad21)") (class "Default")
      (node (ref "CAM1") (pin "21") (pinfunction "21_21") (pintype "passive"))
      (node (ref "JP1") (pin "7") (pinfunction "7_7") (pintype "passive"))
    )
    (net (code "135") (name "Net-(CAM1-Pad22)") (class "Default")
      (node (ref "CAM1") (pin "22") (pinfunction "22_22") (pintype "passive"))
      (node (ref "JP2") (pin "11") (pinfunction "11_11") (pintype "passive"))
    )
    (net (code "136") (name "Net-(CAM1-Pad23)") (class "Default")
      (node (ref "CAM1") (pin "23") (pinfunction "23_23") (pintype "passive"))
      (node (ref "JP1") (pin "6") (pinfunction "6_6") (pintype "passive"))
    )
    (net (code "137") (name "Net-(CAM1-Pad24)") (class "Default")
      (node (ref "CAM1") (pin "24") (pinfunction "24_24") (pintype "passive"))
      (node (ref "JP2") (pin "12") (pinfunction "12_12") (pintype "passive"))
    )
    (net (code "138") (name "Net-(CAM1-Pad25)") (class "Default")
      (node (ref "CAM1") (pin "25") (pinfunction "25_25") (pintype "passive"))
      (node (ref "JP1") (pin "5") (pinfunction "5_5") (pintype "passive"))
    )
    (net (code "139") (name "Net-(CAM1-Pad26)") (class "Default")
      (node (ref "CAM1") (pin "26") (pinfunction "26_26") (pintype "passive"))
      (node (ref "JP2") (pin "13") (pinfunction "13_13") (pintype "passive"))
    )
    (net (code "140") (name "Net-(CAM1-Pad27)") (class "Default")
      (node (ref "CAM1") (pin "27") (pinfunction "27_27") (pintype "passive"))
      (node (ref "JP1") (pin "4") (pinfunction "4_4") (pintype "passive"))
    )
    (net (code "141") (name "Net-(CAM1-Pad28)") (class "Default")
      (node (ref "CAM1") (pin "28") (pinfunction "28_28") (pintype "passive"))
      (node (ref "JP2") (pin "14") (pinfunction "14_14") (pintype "passive"))
    )
    (net (code "142") (name "Net-(CAM1-Pad29)") (class "Default")
      (node (ref "CAM1") (pin "29") (pinfunction "29_29") (pintype "passive"))
      (node (ref "JP1") (pin "3") (pinfunction "3_3") (pintype "passive"))
    )
    (net (code "143") (name "Net-(CAM1-Pad30)") (class "Default")
      (node (ref "CAM1") (pin "30") (pinfunction "30_30") (pintype "passive"))
      (node (ref "JP2") (pin "15") (pinfunction "15_15") (pintype "passive"))
    )
    (net (code "144") (name "Net-(CAM1-Pad31)") (class "Default")
      (node (ref "CAM1") (pin "31") (pinfunction "31_31") (pintype "passive"))
      (node (ref "JP1") (pin "2") (pinfunction "2_2") (pintype "passive"))
    )
    (net (code "145") (name "Net-(CAM1-Pad32)") (class "Default")
      (node (ref "CAM1") (pin "32") (pinfunction "32_32") (pintype "passive"))
      (node (ref "JP2") (pin "16") (pinfunction "16_16") (pintype "passive"))
    )
    (net (code "146") (name "Net-(CAM1-Pad33)") (class "Default")
      (node (ref "CAM1") (pin "33") (pinfunction "33_33") (pintype "passive"))
      (node (ref "JP1") (pin "1") (pinfunction "1_1") (pintype "passive"))
    )
    (net (code "147") (name "Net-(CAM1-Pad34)") (class "Default")
      (node (ref "CAM1") (pin "34") (pinfunction "34_34") (pintype "passive"))
      (node (ref "JP2") (pin "17") (pinfunction "17_17") (pintype "passive"))
    )
    (net (code "148") (name "Net-(CAM2-Pad1)") (class "Default")
      (node (ref "CAM2") (pin "1") (pinfunction "1_1") (pintype "passive"))
      (node (ref "JP4") (pin "17") (pinfunction "17_17") (pintype "passive"))
    )
    (net (code "149") (name "Net-(CAM2-Pad2)") (class "Default")
      (node (ref "CAM2") (pin "2") (pinfunction "2_2") (pintype "passive"))
      (node (ref "JP3") (pin "1") (pinfunction "1_1") (pintype "passive"))
    )
    (net (code "150") (name "Net-(CAM2-Pad3)") (class "Default")
      (node (ref "CAM2") (pin "3") (pinfunction "3_3") (pintype "passive"))
      (node (ref "JP4") (pin "16") (pinfunction "16_16") (pintype "passive"))
    )
    (net (code "151") (name "Net-(CAM2-Pad4)") (class "Default")
      (node (ref "CAM2") (pin "4") (pinfunction "4_4") (pintype "passive"))
      (node (ref "JP3") (pin "2") (pinfunction "2_2") (pintype "passive"))
    )
    (net (code "152") (name "Net-(CAM2-Pad5)") (class "Default")
      (node (ref "CAM2") (pin "5") (pinfunction "5_5") (pintype "passive"))
      (node (ref "JP4") (pin "15") (pinfunction "15_15") (pintype "passive"))
    )
    (net (code "153") (name "Net-(CAM2-Pad6)") (class "Default")
      (node (ref "CAM2") (pin "6") (pinfunction "6_6") (pintype "passive"))
      (node (ref "JP3") (pin "3") (pinfunction "3_3") (pintype "passive"))
    )
    (net (code "154") (name "Net-(CAM2-Pad7)") (class "Default")
      (node (ref "CAM2") (pin "7") (pinfunction "7_7") (pintype "passive"))
      (node (ref "JP4") (pin "14") (pinfunction "14_14") (pintype "passive"))
    )
    (net (code "155") (name "Net-(CAM2-Pad8)") (class "Default")
      (node (ref "CAM2") (pin "8") (pinfunction "8_8") (pintype "passive"))
      (node (ref "JP3") (pin "4") (pinfunction "4_4") (pintype "passive"))
    )
    (net (code "156") (name "Net-(CAM2-Pad9)") (class "Default")
      (node (ref "CAM2") (pin "9") (pinfunction "9_9") (pintype "passive"))
      (node (ref "JP4") (pin "13") (pinfunction "13_13") (pintype "passive"))
    )
    (net (code "157") (name "Net-(CAM2-Pad10)") (class "Default")
      (node (ref "CAM2") (pin "10") (pinfunction "10_10") (pintype "passive"))
      (node (ref "JP3") (pin "5") (pinfunction "5_5") (pintype "passive"))
    )
    (net (code "158") (name "Net-(CAM2-Pad11)") (class "Default")
      (node (ref "CAM2") (pin "11") (pinfunction "11_11") (pintype "passive"))
      (node (ref "JP4") (pin "12") (pinfunction "12_12") (pintype "passive"))
    )
    (net (code "159") (name "Net-(CAM2-Pad12)") (class "Default")
      (node (ref "CAM2") (pin "12") (pinfunction "12_12") (pintype "passive"))
      (node (ref "JP3") (pin "6") (pinfunction "6_6") (pintype "passive"))
    )
    (net (code "160") (name "Net-(CAM2-Pad13)") (class "Default")
      (node (ref "CAM2") (pin "13") (pinfunction "13_13") (pintype "passive"))
      (node (ref "JP4") (pin "11") (pinfunction "11_11") (pintype "passive"))
    )
    (net (code "161") (name "Net-(CAM2-Pad14)") (class "Default")
      (node (ref "CAM2") (pin "14") (pinfunction "14_14") (pintype "passive"))
      (node (ref "JP3") (pin "7") (pinfunction "7_7") (pintype "passive"))
    )
    (net (code "162") (name "Net-(CAM2-Pad15)") (class "Default")
      (node (ref "CAM2") (pin "15") (pinfunction "15_15") (pintype "passive"))
      (node (ref "JP4") (pin "10") (pinfunction "10_10") (pintype "passive"))
    )
    (net (code "163") (name "Net-(CAM2-Pad16)") (class "Default")
      (node (ref "CAM2") (pin "16") (pinfunction "16_16") (pintype "passive"))
      (node (ref "JP3") (pin "8") (pinfunction "8_8") (pintype "passive"))
    )
    (net (code "164") (name "Net-(CAM2-Pad17)") (class "Default")
      (node (ref "CAM2") (pin "17") (pinfunction "17_17") (pintype "passive"))
      (node (ref "JP4") (pin "9") (pinfunction "9_9") (pintype "passive"))
    )
    (net (code "165") (name "Net-(CAM2-Pad18)") (class "Default")
      (node (ref "CAM2") (pin "18") (pinfunction "18_18") (pintype "passive"))
      (node (ref "JP3") (pin "9") (pinfunction "9_9") (pintype "passive"))
    )
    (net (code "166") (name "Net-(CAM2-Pad19)") (class "Default")
      (node (ref "CAM2") (pin "19") (pinfunction "19_19") (pintype "passive"))
      (node (ref "JP4") (pin "8") (pinfunction "8_8") (pintype "passive"))
    )
    (net (code "167") (name "Net-(CAM2-Pad21)") (class "Default")
      (node (ref "CAM2") (pin "21") (pinfunction "21_21") (pintype "passive"))
      (node (ref "JP4") (pin "7") (pinfunction "7_7") (pintype "passive"))
    )
    (net (code "168") (name "Net-(CAM2-Pad22)") (class "Default")
      (node (ref "CAM2") (pin "22") (pinfunction "22_22") (pintype "passive"))
      (node (ref "JP3") (pin "11") (pinfunction "11_11") (pintype "passive"))
    )
    (net (code "169") (name "Net-(CAM2-Pad23)") (class "Default")
      (node (ref "CAM2") (pin "23") (pinfunction "23_23") (pintype "passive"))
      (node (ref "JP4") (pin "6") (pinfunction "6_6") (pintype "passive"))
    )
    (net (code "170") (name "Net-(CAM2-Pad24)") (class "Default")
      (node (ref "CAM2") (pin "24") (pinfunction "24_24") (pintype "passive"))
      (node (ref "JP3") (pin "12") (pinfunction "12_12") (pintype "passive"))
    )
    (net (code "171") (name "Net-(CAM2-Pad26)") (class "Default")
      (node (ref "CAM2") (pin "26") (pinfunction "26_26") (pintype "passive"))
      (node (ref "JP3") (pin "13") (pinfunction "13_13") (pintype "passive"))
    )
    (net (code "172") (name "Net-(CAM2-Pad27)") (class "Default")
      (node (ref "CAM2") (pin "27") (pinfunction "27_27") (pintype "passive"))
      (node (ref "JP4") (pin "4") (pinfunction "4_4") (pintype "passive"))
    )
    (net (code "173") (name "Net-(CAM2-Pad28)") (class "Default")
      (node (ref "CAM2") (pin "28") (pinfunction "28_28") (pintype "passive"))
      (node (ref "JP3") (pin "14") (pinfunction "14_14") (pintype "passive"))
    )
    (net (code "174") (name "Net-(CAM2-Pad29)") (class "Default")
      (node (ref "CAM2") (pin "29") (pinfunction "29_29") (pintype "passive"))
      (node (ref "JP4") (pin "3") (pinfunction "3_3") (pintype "passive"))
    )
    (net (code "175") (name "Net-(CAM2-Pad30)") (class "Default")
      (node (ref "CAM2") (pin "30") (pinfunction "30_30") (pintype "passive"))
      (node (ref "JP3") (pin "15") (pinfunction "15_15") (pintype "passive"))
    )
    (net (code "176") (name "Net-(CAM2-Pad31)") (class "Default")
      (node (ref "CAM2") (pin "31") (pinfunction "31_31") (pintype "passive"))
      (node (ref "JP4") (pin "2") (pinfunction "2_2") (pintype "passive"))
    )
    (net (code "177") (name "Net-(CAM2-Pad32)") (class "Default")
      (node (ref "CAM2") (pin "32") (pinfunction "32_32") (pintype "passive"))
      (node (ref "JP3") (pin "16") (pinfunction "16_16") (pintype "passive"))
    )
    (net (code "178") (name "Net-(CAM2-Pad33)") (class "Default")
      (node (ref "CAM2") (pin "33") (pinfunction "33_33") (pintype "passive"))
      (node (ref "JP4") (pin "1") (pinfunction "1_1") (pintype "passive"))
    )
    (net (code "179") (name "Net-(CAM2-Pad34)") (class "Default")
      (node (ref "CAM2") (pin "34") (pinfunction "34_34") (pintype "passive"))
      (node (ref "JP3") (pin "17") (pinfunction "17_17") (pintype "passive"))
    )
    (net (code "180") (name "unconnected-(CAM1_IN-Pad16)") (class "Default")
      (node (ref "CAM1_IN") (pin "16") (pinfunction "16_16") (pintype "passive"))
    )
    (net (code "181") (name "unconnected-(CAM1_IN-Pad17)") (class "Default")
      (node (ref "CAM1_IN") (pin "17") (pinfunction "17_17") (pintype "passive"))
    )
    (net (code "182") (name "unconnected-(CAM1_IN-Pad18)") (class "Default")
      (node (ref "CAM1_IN") (pin "18") (pinfunction "18_18") (pintype "passive"))
    )
    (net (code "183") (name "unconnected-(CAM1_IN-Pad19)") (class "Default")
      (node (ref "CAM1_IN") (pin "19") (pinfunction "19_19") (pintype "passive"))
    )
    (net (code "184") (name "unconnected-(CAM1_IN-Pad21)") (class "Default")
      (node (ref "CAM1_IN") (pin "21") (pinfunction "21_21") (pintype "passive"))
    )
    (net (code "185") (name "unconnected-(CAM1_IN-Pad23)") (class "Default")
      (node (ref "CAM1_IN") (pin "23") (pinfunction "23_23") (pintype "passive"))
    )
    (net (code "186") (name "unconnected-(CAM1_IN-Pad24)") (class "Default")
      (node (ref "CAM1_IN") (pin "24") (pinfunction "24_24") (pintype "passive"))
    )
    (net (code "187") (name "unconnected-(CAM1_IN-Pad30)") (class "Default")
      (node (ref "CAM1_IN") (pin "30") (pinfunction "30_30") (pintype "passive"))
    )
    (net (code "188") (name "unconnected-(CAM1_IN-Pad32)") (class "Default")
      (node (ref "CAM1_IN") (pin "32") (pinfunction "32_32") (pintype "passive"))
    )
    (net (code "189") (name "unconnected-(CAM1_IN-Pad33)") (class "Default")
      (node (ref "CAM1_IN") (pin "33") (pinfunction "33_33") (pintype "passive"))
    )
    (net (code "190") (name "unconnected-(CAM1_IN-Pad34)") (class "Default")
      (node (ref "CAM1_IN") (pin "34") (pinfunction "34_34") (pintype "passive"))
    )
    (net (code "191") (name "unconnected-(CAM2-Pad20)") (class "Default")
      (node (ref "CAM2") (pin "20") (pinfunction "20_20") (pintype "passive"))
    )
    (net (code "192") (name "unconnected-(CAM2-Pad25)") (class "Default")
      (node (ref "CAM2") (pin "25") (pinfunction "25_25") (pintype "passive"))
    )
    (net (code "193") (name "unconnected-(CAM2_IN-Pad16)") (class "Default")
      (node (ref "CAM2_IN") (pin "16") (pinfunction "16_16") (pintype "passive"))
    )
    (net (code "194") (name "unconnected-(CAM2_IN-Pad17)") (class "Default")
      (node (ref "CAM2_IN") (pin "17") (pinfunction "17_17") (pintype "passive"))
    )
    (net (code "195") (name "unconnected-(CAM2_IN-Pad18)") (class "Default")
      (node (ref "CAM2_IN") (pin "18") (pinfunction "18_18") (pintype "passive"))
    )
    (net (code "196") (name "unconnected-(CAM2_IN-Pad19)") (class "Default")
      (node (ref "CAM2_IN") (pin "19") (pinfunction "19_19") (pintype "passive"))
    )
    (net (code "197") (name "unconnected-(CAM2_IN-Pad21)") (class "Default")
      (node (ref "CAM2_IN") (pin "21") (pinfunction "21_21") (pintype "passive"))
    )
    (net (code "198") (name "unconnected-(CAM2_IN-Pad23)") (class "Default")
      (node (ref "CAM2_IN") (pin "23") (pinfunction "23_23") (pintype "passive"))
    )
    (net (code "199") (name "unconnected-(CAM2_IN-Pad24)") (class "Default")
      (node (ref "CAM2_IN") (pin "24") (pinfunction "24_24") (pintype "passive"))
    )
    (net (code "200") (name "unconnected-(CAM2_IN-Pad30)") (class "Default")
      (node (ref "CAM2_IN") (pin "30") (pinfunction "30_30") (pintype "passive"))
    )
    (net (code "201") (name "unconnected-(CAM2_IN-Pad32)") (class "Default")
      (node (ref "CAM2_IN") (pin "32") (pinfunction "32_32") (pintype "passive"))
    )
    (net (code "202") (name "unconnected-(CAM2_IN-Pad33)") (class "Default")
      (node (ref "CAM2_IN") (pin "33") (pinfunction "33_33") (pintype "passive"))
    )
    (net (code "203") (name "unconnected-(CAM2_IN-Pad34)") (class "Default")
      (node (ref "CAM2_IN") (pin "34") (pinfunction "34_34") (pintype "passive"))
    )
    (net (code "204") (name "unconnected-(JP3-Pad10)") (class "Default")
      (node (ref "JP3") (pin "10") (pinfunction "10_10") (pintype "passive"))
    )
    (net (code "205") (name "unconnected-(JP4-Pad5)") (class "Default")
      (node (ref "JP4") (pin "5") (pinfunction "5_5") (pintype "passive"))
    )
  )
)
